# darwin-sonar-module.net
KiCad netlist of a schematic drawn in EAGLE
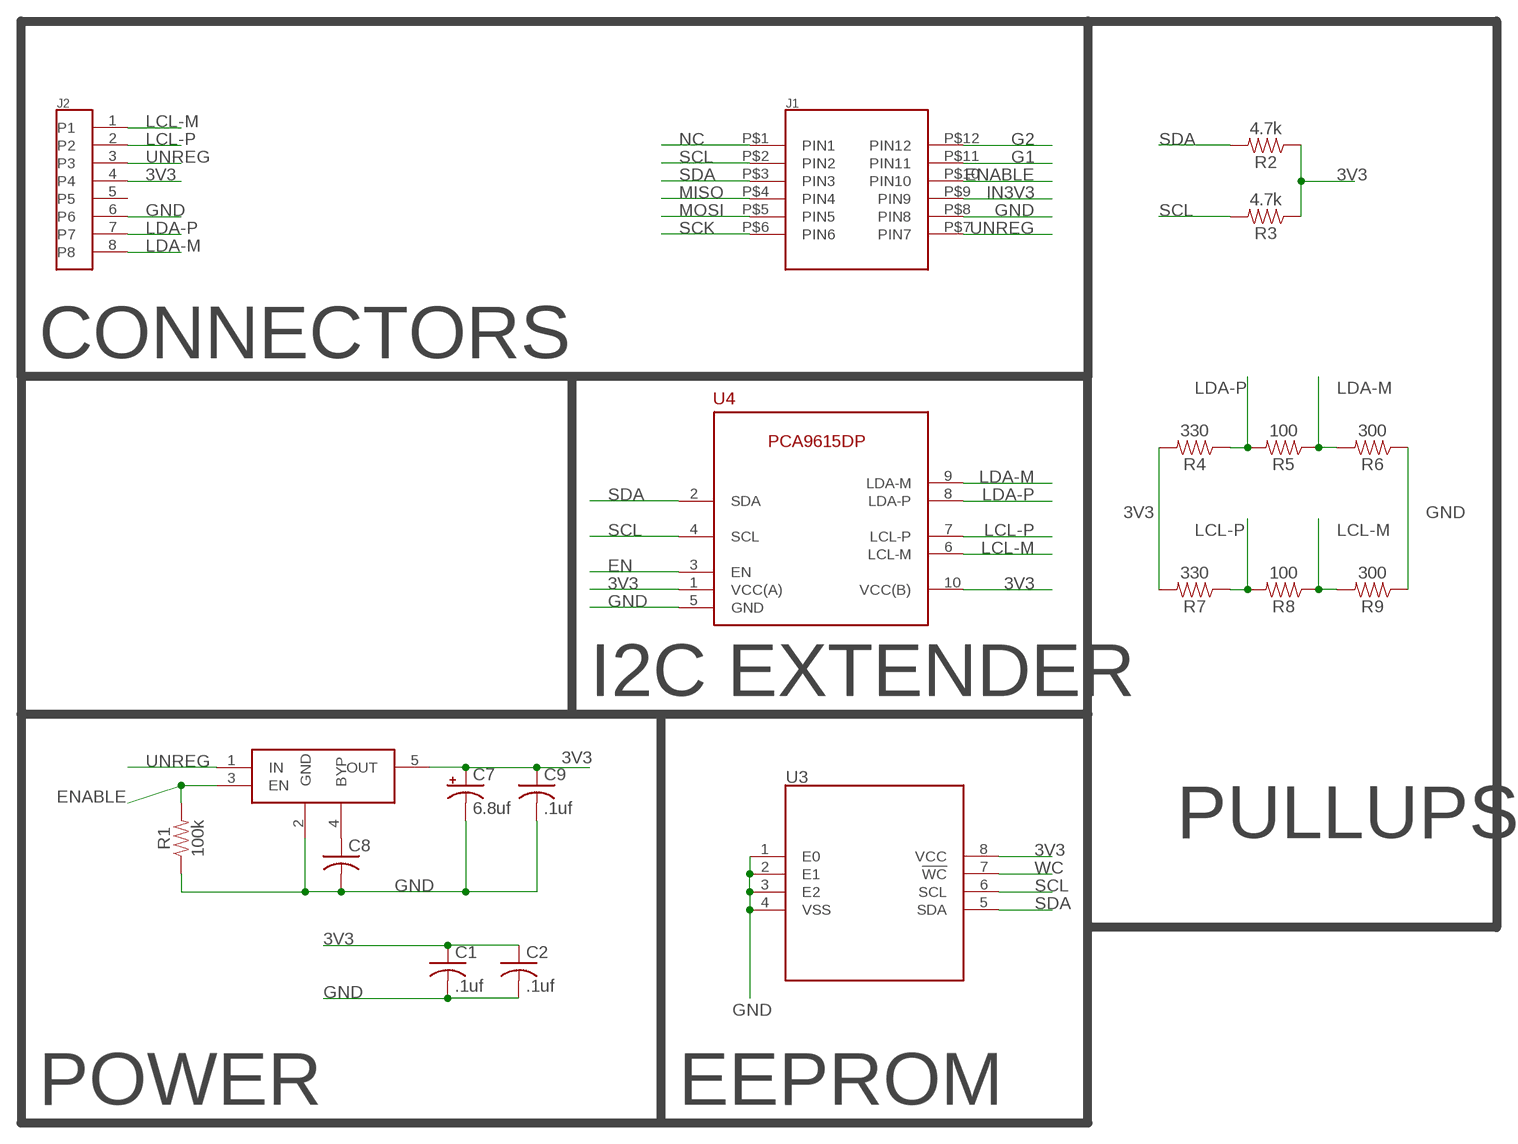
[diagram p0: schematic, sheet 1]

(export (version "E")
  (design (tool "Eeschema 10.0.6"))
  (components
    (comp (ref "C1")
      (value ".1uf")
      (footprint "eagle-import:C0603K")
      (libsource (lib "eagle-import") (part "C-USC0603K"))
    )
    (comp (ref "C2")
      (value ".1uf")
      (footprint "eagle-import:C0603K")
      (libsource (lib "eagle-import") (part "C-USC0603K"))
    )
    (comp (ref "C7")
      (value "6.8uf")
      (footprint "eagle-import:A_3216-18R")
      (libsource (lib "eagle-import") (part "CPOL-USA/3216-18R"))
    )
    (comp (ref "C8")
      (value "C-USC0603K")
      (footprint "eagle-import:C0603K")
      (libsource (lib "eagle-import") (part "C-USC0603K"))
    )
    (comp (ref "C9")
      (value ".1uf")
      (footprint "eagle-import:C0603K")
      (libsource (lib "eagle-import") (part "C-USC0603K"))
    )
    (comp (ref "J1")
      (value "2X6-HEADERS")
      (footprint "eagle-import:M20-7810645")
      (libsource (lib "eagle-import") (part "2X6-HEADERS"))
    )
    (comp (ref "J2")
      (value "95501-6889VERT")
      (footprint "eagle-import:85513-5009")
      (libsource (lib "eagle-import") (part "95501-6889VERT"))
    )
    (comp (ref "R1")
      (value "100k")
      (footprint "eagle-import:0603")
      (libsource (lib "eagle-import") (part "100KOHM-0603-1/10W-1%"))
    )
    (comp (ref "R2")
      (value "4.7k")
      (footprint "eagle-import:0603")
      (libsource (lib "eagle-import") (part "100KOHM-0603-1/10W-1%"))
    )
    (comp (ref "R3")
      (value "4.7k")
      (footprint "eagle-import:0603")
      (libsource (lib "eagle-import") (part "100KOHM-0603-1/10W-1%"))
    )
    (comp (ref "R4")
      (value "330")
      (footprint "eagle-import:0603")
      (libsource (lib "eagle-import") (part "100KOHM-0603-1/10W-1%"))
    )
    (comp (ref "R5")
      (value "100")
      (footprint "eagle-import:0603")
      (libsource (lib "eagle-import") (part "100KOHM-0603-1/10W-1%"))
    )
    (comp (ref "R6")
      (value "300")
      (footprint "eagle-import:0603")
      (libsource (lib "eagle-import") (part "100KOHM-0603-1/10W-1%"))
    )
    (comp (ref "R7")
      (value "330")
      (footprint "eagle-import:0603")
      (libsource (lib "eagle-import") (part "100KOHM-0603-1/10W-1%"))
    )
    (comp (ref "R8")
      (value "100")
      (footprint "eagle-import:0603")
      (libsource (lib "eagle-import") (part "100KOHM-0603-1/10W-1%"))
    )
    (comp (ref "R9")
      (value "300")
      (footprint "eagle-import:0603")
      (libsource (lib "eagle-import") (part "100KOHM-0603-1/10W-1%"))
    )
    (comp (ref "U$4")
      (value "MIC5219-3.3YM5-TR")
      (footprint "eagle-import:SOT95P280X145-5")
      (libsource (lib "eagle-import") (part "MIC5219-3.3YM5-TR"))
    )
    (comp (ref "U3")
      (value "M24C02-WMN6TP")
      (footprint "eagle-import:SOIC127P600X175-8")
      (libsource (lib "eagle-import") (part "M24C02-WMN6TP"))
    )
    (comp (ref "U4")
      (value "PCA9615")
      (footprint "eagle-import:SOP50P490X110-10")
      (libsource (lib "eagle-import") (part "PCA9615"))
    )
  )
  (nets
    (net (code "1") (name "/3V3") (class "Default")
      (node (ref "C1") (pin "1") (pinfunction "1_1") (pintype "passive"))
      (node (ref "C2") (pin "1") (pinfunction "1_1") (pintype "passive"))
      (node (ref "C7") (pin "+") (pinfunction "+_+") (pintype "passive"))
      (node (ref "C9") (pin "1") (pinfunction "1_1") (pintype "passive"))
      (node (ref "J2") (pin "4") (pinfunction "P4_4") (pintype "bidirectional"))
      (node (ref "R2") (pin "1") (pinfunction "1_1") (pintype "passive"))
      (node (ref "R3") (pin "1") (pinfunction "1_1") (pintype "passive"))
      (node (ref "R4") (pin "2") (pinfunction "2_2") (pintype "passive"))
      (node (ref "R7") (pin "2") (pinfunction "2_2") (pintype "passive"))
      (node (ref "U$4") (pin "5") (pinfunction "OUT_5") (pintype "bidirectional"))
      (node (ref "U3") (pin "8") (pinfunction "VCC_8") (pintype "bidirectional"))
      (node (ref "U4") (pin "1") (pinfunction "VCC(A)_1") (pintype "bidirectional"))
      (node (ref "U4") (pin "10") (pinfunction "VCC(B)_10") (pintype "bidirectional"))
    )
    (net (code "2") (name "/EN") (class "Default")
      (node (ref "U4") (pin "3") (pinfunction "EN_3") (pintype "bidirectional"))
    )
    (net (code "3") (name "/ENABLE") (class "Default")
      (node (ref "J1") (pin "P$10") (pinfunction "PIN10_P$10") (pintype "bidirectional"))
      (node (ref "R1") (pin "2") (pinfunction "2_2") (pintype "passive"))
      (node (ref "U$4") (pin "3") (pinfunction "EN_3") (pintype "bidirectional"))
    )
    (net (code "4") (name "/G1") (class "Default")
      (node (ref "J1") (pin "P$11") (pinfunction "PIN11_P$11") (pintype "bidirectional"))
    )
    (net (code "5") (name "/G2") (class "Default")
      (node (ref "J1") (pin "P$12") (pinfunction "PIN12_P$12") (pintype "bidirectional"))
    )
    (net (code "6") (name "/GND") (class "Default")
      (node (ref "C1") (pin "2") (pinfunction "2_2") (pintype "passive"))
      (node (ref "C2") (pin "2") (pinfunction "2_2") (pintype "passive"))
      (node (ref "C7") (pin "-") (pinfunction "-_-") (pintype "passive"))
      (node (ref "C8") (pin "2") (pinfunction "2_2") (pintype "passive"))
      (node (ref "C9") (pin "2") (pinfunction "2_2") (pintype "passive"))
      (node (ref "J1") (pin "P$8") (pinfunction "PIN8_P$8") (pintype "bidirectional"))
      (node (ref "J2") (pin "6") (pinfunction "P6_6") (pintype "bidirectional"))
      (node (ref "R1") (pin "1") (pinfunction "1_1") (pintype "passive"))
      (node (ref "R6") (pin "1") (pinfunction "1_1") (pintype "passive"))
      (node (ref "R9") (pin "1") (pinfunction "1_1") (pintype "passive"))
      (node (ref "U$4") (pin "2") (pinfunction "GND_2") (pintype "bidirectional"))
      (node (ref "U3") (pin "1") (pinfunction "E0_1") (pintype "bidirectional"))
      (node (ref "U3") (pin "2") (pinfunction "E1_2") (pintype "bidirectional"))
      (node (ref "U3") (pin "3") (pinfunction "E2_3") (pintype "bidirectional"))
      (node (ref "U3") (pin "4") (pinfunction "VSS_4") (pintype "bidirectional"))
      (node (ref "U4") (pin "5") (pinfunction "GND_5") (pintype "bidirectional"))
    )
    (net (code "7") (name "/IN3V3") (class "Default")
      (node (ref "J1") (pin "P$9") (pinfunction "PIN9_P$9") (pintype "bidirectional"))
    )
    (net (code "8") (name "/LCL-M") (class "Default")
      (node (ref "J2") (pin "1") (pinfunction "P1_1") (pintype "bidirectional"))
      (node (ref "R8") (pin "1") (pinfunction "1_1") (pintype "passive"))
      (node (ref "R9") (pin "2") (pinfunction "2_2") (pintype "passive"))
      (node (ref "U4") (pin "6") (pinfunction "LCL-M_6") (pintype "bidirectional"))
    )
    (net (code "9") (name "/LCL-P") (class "Default")
      (node (ref "J2") (pin "2") (pinfunction "P2_2") (pintype "bidirectional"))
      (node (ref "R7") (pin "1") (pinfunction "1_1") (pintype "passive"))
      (node (ref "R8") (pin "2") (pinfunction "2_2") (pintype "passive"))
      (node (ref "U4") (pin "7") (pinfunction "LCL-P_7") (pintype "bidirectional"))
    )
    (net (code "10") (name "/LDA-M") (class "Default")
      (node (ref "J2") (pin "8") (pinfunction "P8_8") (pintype "bidirectional"))
      (node (ref "R5") (pin "1") (pinfunction "1_1") (pintype "passive"))
      (node (ref "R6") (pin "2") (pinfunction "2_2") (pintype "passive"))
      (node (ref "U4") (pin "9") (pinfunction "LDA-M_9") (pintype "bidirectional"))
    )
    (net (code "11") (name "/LDA-P") (class "Default")
      (node (ref "J2") (pin "7") (pinfunction "P7_7") (pintype "bidirectional"))
      (node (ref "R4") (pin "1") (pinfunction "1_1") (pintype "passive"))
      (node (ref "R5") (pin "2") (pinfunction "2_2") (pintype "passive"))
      (node (ref "U4") (pin "8") (pinfunction "LDA-P_8") (pintype "bidirectional"))
    )
    (net (code "12") (name "/MISO") (class "Default")
      (node (ref "J1") (pin "P$4") (pinfunction "PIN4_P$4") (pintype "bidirectional"))
    )
    (net (code "13") (name "/MOSI") (class "Default")
      (node (ref "J1") (pin "P$5") (pinfunction "PIN5_P$5") (pintype "bidirectional"))
    )
    (net (code "14") (name "/NC") (class "Default")
      (node (ref "J1") (pin "P$1") (pinfunction "PIN1_P$1") (pintype "bidirectional"))
    )
    (net (code "15") (name "/SCK") (class "Default")
      (node (ref "J1") (pin "P$6") (pinfunction "PIN6_P$6") (pintype "bidirectional"))
    )
    (net (code "16") (name "/SCL") (class "Default")
      (node (ref "J1") (pin "P$2") (pinfunction "PIN2_P$2") (pintype "bidirectional"))
      (node (ref "R3") (pin "2") (pinfunction "2_2") (pintype "passive"))
      (node (ref "U3") (pin "6") (pinfunction "SCL_6") (pintype "bidirectional"))
      (node (ref "U4") (pin "4") (pinfunction "SCL_4") (pintype "bidirectional"))
    )
    (net (code "17") (name "/SDA") (class "Default")
      (node (ref "J1") (pin "P$3") (pinfunction "PIN3_P$3") (pintype "bidirectional"))
      (node (ref "R2") (pin "2") (pinfunction "2_2") (pintype "passive"))
      (node (ref "U3") (pin "5") (pinfunction "SDA_5") (pintype "bidirectional"))
      (node (ref "U4") (pin "2") (pinfunction "SDA_2") (pintype "bidirectional"))
    )
    (net (code "18") (name "/UNREG") (class "Default")
      (node (ref "J1") (pin "P$7") (pinfunction "PIN7_P$7") (pintype "bidirectional"))
      (node (ref "J2") (pin "3") (pinfunction "P3_3") (pintype "bidirectional"))
      (node (ref "U$4") (pin "1") (pinfunction "IN_1") (pintype "bidirectional"))
    )
    (net (code "19") (name "/WC") (class "Default")
      (node (ref "U3") (pin "7") (pinfunction "~{WC}_7") (pintype "bidirectional"))
    )
    (net (code "20") (name "Net-(U$4-BYP)") (class "Default")
      (node (ref "C8") (pin "1") (pinfunction "1_1") (pintype "passive"))
      (node (ref "U$4") (pin "4") (pinfunction "BYP_4") (pintype "bidirectional"))
    )
    (net (code "21") (name "unconnected-(J2-P5-Pad5)") (class "Default")
      (node (ref "J2") (pin "5") (pinfunction "P5_5") (pintype "bidirectional"))
    )
  )
)
